# 4ButtonSwitch_Rev2_2.net
KiCad netlist of a schematic drawn in EAGLE
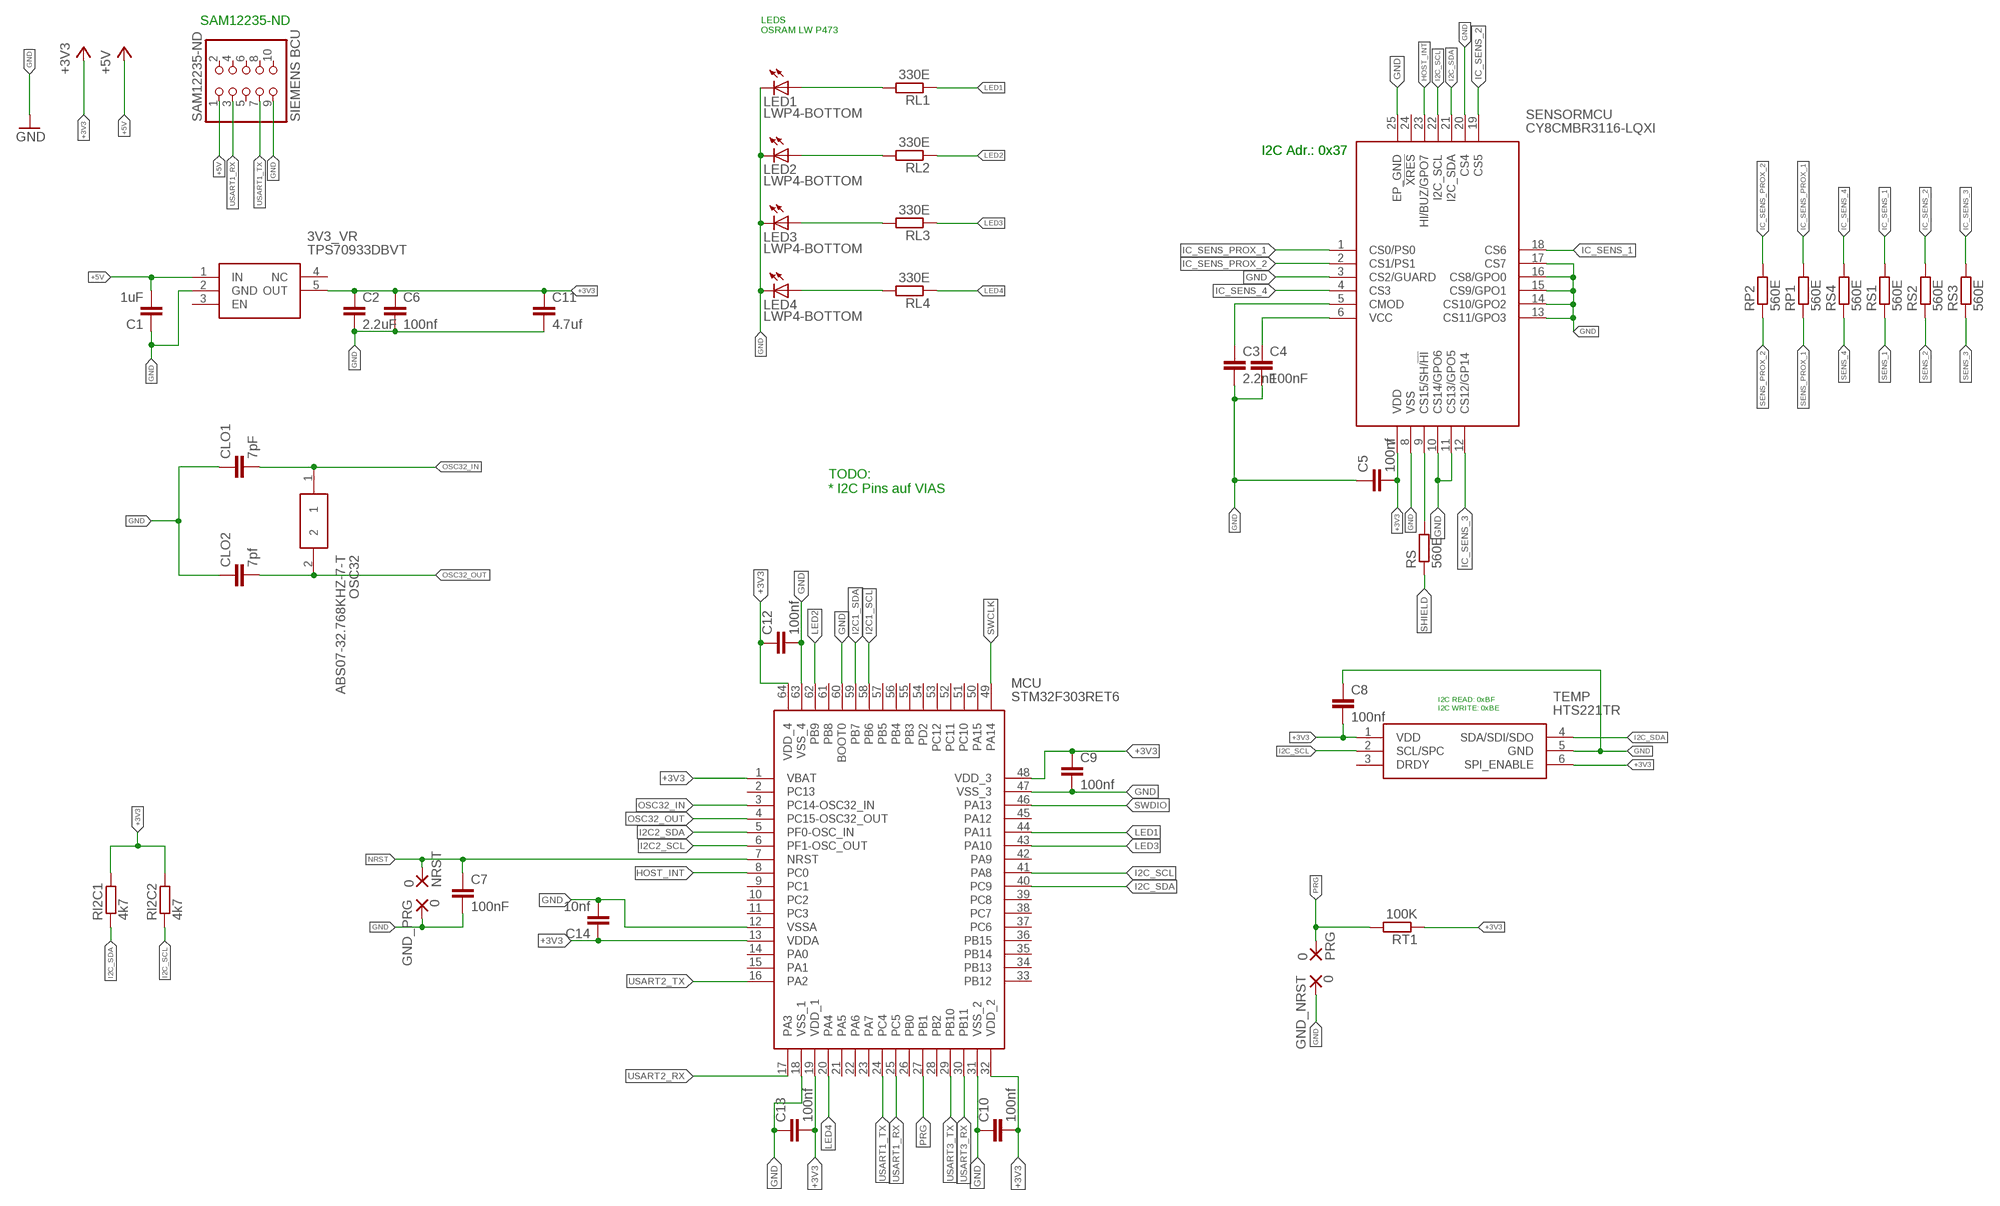
[diagram p0: schematic, sheet 1]

(export (version "E")
  (design (tool "Eeschema 10.0.6"))
  (components
    (comp (ref "3V3_VR")
      (value "TPS70933DBVT")
      (footprint "eagle-import:SOT95P280X145-5N")
      (fields (field (name "RS_PART_NUMBER") "8257033P"))
      (libsource (lib "eagle-import") (part "TPS70933DBVT"))
    )
    (comp (ref "C1")
      (value "1uF")
      (footprint "eagle-import:C0402")
      (libsource (lib "eagle-import") (part "C-EUC0402"))
    )
    (comp (ref "C2")
      (value "2.2uF")
      (footprint "eagle-import:C0402")
      (libsource (lib "eagle-import") (part "C-EUC0402"))
    )
    (comp (ref "C3")
      (value "2.2nF")
      (footprint "eagle-import:C0402")
      (libsource (lib "eagle-import") (part "C-EUC0402"))
    )
    (comp (ref "C4")
      (value "100nF")
      (footprint "eagle-import:C0402")
      (libsource (lib "eagle-import") (part "C-EUC0402"))
    )
    (comp (ref "C5")
      (value "100nf")
      (footprint "eagle-import:C0402")
      (libsource (lib "eagle-import") (part "C-EUC0402"))
    )
    (comp (ref "C6")
      (value "100nf")
      (footprint "eagle-import:C0402")
      (libsource (lib "eagle-import") (part "C-EUC0402"))
    )
    (comp (ref "C7")
      (value "100nF")
      (footprint "eagle-import:C0402")
      (libsource (lib "eagle-import") (part "C-EUC0402"))
    )
    (comp (ref "C8")
      (value "100nf")
      (footprint "eagle-import:C0402")
      (libsource (lib "eagle-import") (part "C-EUC0402"))
    )
    (comp (ref "C9")
      (value "100nf")
      (footprint "eagle-import:C0402")
      (libsource (lib "eagle-import") (part "C-EUC0402"))
    )
    (comp (ref "C10")
      (value "100nf")
      (footprint "eagle-import:C0402")
      (libsource (lib "eagle-import") (part "C-EUC0402"))
    )
    (comp (ref "C11")
      (value "4.7uf")
      (footprint "eagle-import:C0402")
      (libsource (lib "eagle-import") (part "C-EUC0402"))
    )
    (comp (ref "C12")
      (value "100nf")
      (footprint "eagle-import:C0402")
      (libsource (lib "eagle-import") (part "C-EUC0402"))
    )
    (comp (ref "C13")
      (value "100nf")
      (footprint "eagle-import:C0402")
      (libsource (lib "eagle-import") (part "C-EUC0402"))
    )
    (comp (ref "C14")
      (value "10nf")
      (footprint "eagle-import:C0402")
      (libsource (lib "eagle-import") (part "C-EUC0402"))
    )
    (comp (ref "CLO1")
      (value "7pF")
      (footprint "eagle-import:C0402")
      (libsource (lib "eagle-import") (part "C-EUC0402"))
    )
    (comp (ref "CLO2")
      (value "7pf")
      (footprint "eagle-import:C0402")
      (libsource (lib "eagle-import") (part "C-EUC0402"))
    )
    (comp (ref "GND_NRST")
      (value "0")
      (footprint "eagle-import:SMD2,54-5,08")
      (libsource (lib "eagle-import") (part "SMD5"))
    )
    (comp (ref "GND_PRG")
      (value "0")
      (footprint "eagle-import:SMD2,54-5,08")
      (libsource (lib "eagle-import") (part "SMD5"))
    )
    (comp (ref "LED1")
      (value "LWP4-BOTTOM")
      (footprint "eagle-import:P47F-BOTTOM")
      (libsource (lib "eagle-import") (part "P4-BOTTOMLW"))
    )
    (comp (ref "LED2")
      (value "LWP4-BOTTOM")
      (footprint "eagle-import:P47F-BOTTOM")
      (libsource (lib "eagle-import") (part "P4-BOTTOMLW"))
    )
    (comp (ref "LED3")
      (value "LWP4-BOTTOM")
      (footprint "eagle-import:P47F-BOTTOM")
      (libsource (lib "eagle-import") (part "P4-BOTTOMLW"))
    )
    (comp (ref "LED4")
      (value "LWP4-BOTTOM")
      (footprint "eagle-import:P47F-BOTTOM")
      (libsource (lib "eagle-import") (part "P4-BOTTOMLW"))
    )
    (comp (ref "MCU")
      (value "STM32F303RET6")
      (footprint "eagle-import:QFP50P1200X1200X160-64N")
      (fields (field (name "RS_PART_NUMBER") "1458887"))
      (libsource (lib "eagle-import") (part "STM32F303RET6"))
    )
    (comp (ref "NRST")
      (value "0")
      (footprint "eagle-import:SMD2,54-5,08")
      (libsource (lib "eagle-import") (part "SMD5"))
    )
    (comp (ref "OSC32")
      (value "ABS07-32.768KHZ-7-T")
      (footprint "eagle-import:ABS-07")
      (fields (field (name "RS_PART_NUMBER") "1712773P"))
      (libsource (lib "eagle-import") (part "ABS07-32.768KHZ-7-T"))
    )
    (comp (ref "PRG")
      (value "0")
      (footprint "eagle-import:SMD2,54-5,08")
      (libsource (lib "eagle-import") (part "SMD5"))
    )
    (comp (ref "RI2C1")
      (value "4k7")
      (footprint "eagle-import:R0402")
      (libsource (lib "eagle-import") (part "R-EU_R0402"))
    )
    (comp (ref "RI2C2")
      (value "4k7")
      (footprint "eagle-import:R0402")
      (libsource (lib "eagle-import") (part "R-EU_R0402"))
    )
    (comp (ref "RL1")
      (value "330E")
      (footprint "eagle-import:R0402")
      (libsource (lib "eagle-import") (part "R-EU_R0402"))
    )
    (comp (ref "RL2")
      (value "330E")
      (footprint "eagle-import:R0402")
      (libsource (lib "eagle-import") (part "R-EU_R0402"))
    )
    (comp (ref "RL3")
      (value "330E")
      (footprint "eagle-import:R0402")
      (libsource (lib "eagle-import") (part "R-EU_R0402"))
    )
    (comp (ref "RL4")
      (value "330E")
      (footprint "eagle-import:R0402")
      (libsource (lib "eagle-import") (part "R-EU_R0402"))
    )
    (comp (ref "RP1")
      (value "560E")
      (footprint "eagle-import:R0402")
      (libsource (lib "eagle-import") (part "R-EU_R0402"))
    )
    (comp (ref "RP2")
      (value "560E")
      (footprint "eagle-import:R0402")
      (libsource (lib "eagle-import") (part "R-EU_R0402"))
    )
    (comp (ref "RS")
      (value "560E")
      (footprint "eagle-import:R0402")
      (libsource (lib "eagle-import") (part "R-EU_R0402"))
    )
    (comp (ref "RS1")
      (value "560E")
      (footprint "eagle-import:R0402")
      (libsource (lib "eagle-import") (part "R-EU_R0402"))
    )
    (comp (ref "RS2")
      (value "560E")
      (footprint "eagle-import:R0402")
      (libsource (lib "eagle-import") (part "R-EU_R0402"))
    )
    (comp (ref "RS3")
      (value "560E")
      (footprint "eagle-import:R0402")
      (libsource (lib "eagle-import") (part "R-EU_R0402"))
    )
    (comp (ref "RS4")
      (value "560E")
      (footprint "eagle-import:R0402")
      (libsource (lib "eagle-import") (part "R-EU_R0402"))
    )
    (comp (ref "RT1")
      (value "100K")
      (footprint "eagle-import:R0402")
      (libsource (lib "eagle-import") (part "R-EU_R0402"))
    )
    (comp (ref "SAM12235-ND")
      (value "SIEMENS BCU")
      (footprint "eagle-import:2X05SMD")
      (libsource (lib "eagle-import") (part "PINHD-2X5_2.54-SMD"))
    )
    (comp (ref "SENSORMCU")
      (value "CY8CMBR3116-LQXI")
      (footprint "eagle-import:QFN50P400X400X60-25N")
      (fields (field (name "RS_PART_NUMBER") "1242976P"))
      (libsource (lib "eagle-import") (part "CY8CMBR3116-LQXI"))
    )
    (comp (ref "TEMP")
      (value "HTS221TR")
      (footprint "eagle-import:HLGA-6L")
      (fields (field (name "RS_PART_NUMBER") "1660935"))
      (libsource (lib "eagle-import") (part "HTS221TR"))
    )
  )
  (nets
    (net (code "1") (name "+3V3") (class "Default")
      (node (ref "3V3_VR") (pin "5") (pinfunction "OUT_5") (pintype "bidirectional"))
      (node (ref "C10") (pin "2") (pinfunction "2_2") (pintype "passive"))
      (node (ref "C11") (pin "1") (pinfunction "1_1") (pintype "passive"))
      (node (ref "C12") (pin "1") (pinfunction "1_1") (pintype "passive"))
      (node (ref "C13") (pin "2") (pinfunction "2_2") (pintype "passive"))
      (node (ref "C14") (pin "1") (pinfunction "1_1") (pintype "passive"))
      (node (ref "C2") (pin "1") (pinfunction "1_1") (pintype "passive"))
      (node (ref "C5") (pin "2") (pinfunction "2_2") (pintype "passive"))
      (node (ref "C6") (pin "1") (pinfunction "1_1") (pintype "passive"))
      (node (ref "C8") (pin "2") (pinfunction "2_2") (pintype "passive"))
      (node (ref "C9") (pin "1") (pinfunction "1_1") (pintype "passive"))
      (node (ref "MCU") (pin "1") (pinfunction "VBAT_1") (pintype "power_in"))
      (node (ref "MCU") (pin "13") (pinfunction "VDDA_13") (pintype "power_in"))
      (node (ref "MCU") (pin "19") (pinfunction "VDD_1_19") (pintype "power_in"))
      (node (ref "MCU") (pin "32") (pinfunction "VDD_2_32") (pintype "power_in"))
      (node (ref "MCU") (pin "48") (pinfunction "VDD_3_48") (pintype "power_in"))
      (node (ref "MCU") (pin "64") (pinfunction "VDD_4_64") (pintype "power_in"))
      (node (ref "RI2C1") (pin "2") (pinfunction "2_2") (pintype "passive"))
      (node (ref "RI2C2") (pin "2") (pinfunction "2_2") (pintype "passive"))
      (node (ref "RT1") (pin "1") (pinfunction "1_1") (pintype "passive"))
      (node (ref "SENSORMCU") (pin "7") (pinfunction "VDD_7") (pintype "power_in"))
      (node (ref "TEMP") (pin "1") (pinfunction "VDD_1") (pintype "bidirectional"))
      (node (ref "TEMP") (pin "6") (pinfunction "SPI_ENABLE_6") (pintype "bidirectional"))
    )
    (net (code "2") (name "+5V") (class "Default")
      (node (ref "3V3_VR") (pin "1") (pinfunction "IN_1") (pintype "bidirectional"))
      (node (ref "C1") (pin "2") (pinfunction "2_2") (pintype "passive"))
      (node (ref "SAM12235-ND") (pin "1") (pinfunction "1_1") (pintype "passive"))
    )
    (net (code "3") (name "GND") (class "Default")
      (node (ref "3V3_VR") (pin "2") (pinfunction "GND_2") (pintype "bidirectional"))
      (node (ref "C1") (pin "1") (pinfunction "1_1") (pintype "passive"))
      (node (ref "C10") (pin "1") (pinfunction "1_1") (pintype "passive"))
      (node (ref "C11") (pin "2") (pinfunction "2_2") (pintype "passive"))
      (node (ref "C12") (pin "2") (pinfunction "2_2") (pintype "passive"))
      (node (ref "C13") (pin "1") (pinfunction "1_1") (pintype "passive"))
      (node (ref "C14") (pin "2") (pinfunction "2_2") (pintype "passive"))
      (node (ref "C2") (pin "2") (pinfunction "2_2") (pintype "passive"))
      (node (ref "C3") (pin "2") (pinfunction "2_2") (pintype "passive"))
      (node (ref "C4") (pin "2") (pinfunction "2_2") (pintype "passive"))
      (node (ref "C5") (pin "1") (pinfunction "1_1") (pintype "passive"))
      (node (ref "C6") (pin "2") (pinfunction "2_2") (pintype "passive"))
      (node (ref "C7") (pin "2") (pinfunction "2_2") (pintype "passive"))
      (node (ref "C8") (pin "1") (pinfunction "1_1") (pintype "passive"))
      (node (ref "C9") (pin "2") (pinfunction "2_2") (pintype "passive"))
      (node (ref "CLO1") (pin "1") (pinfunction "1_1") (pintype "passive"))
      (node (ref "CLO2") (pin "1") (pinfunction "1_1") (pintype "passive"))
      (node (ref "GND_NRST") (pin "1") (pinfunction "P_1") (pintype "passive"))
      (node (ref "GND_PRG") (pin "1") (pinfunction "P_1") (pintype "passive"))
      (node (ref "LED1") (pin "C") (pinfunction "C_C") (pintype "passive"))
      (node (ref "LED2") (pin "C") (pinfunction "C_C") (pintype "passive"))
      (node (ref "LED3") (pin "C") (pinfunction "C_C") (pintype "passive"))
      (node (ref "LED4") (pin "C") (pinfunction "C_C") (pintype "passive"))
      (node (ref "MCU") (pin "12") (pinfunction "VSSA_12") (pintype "power_in"))
      (node (ref "MCU") (pin "18") (pinfunction "VSS_1_18") (pintype "power_in"))
      (node (ref "MCU") (pin "31") (pinfunction "VSS_2_31") (pintype "power_in"))
      (node (ref "MCU") (pin "47") (pinfunction "VSS_3_47") (pintype "power_in"))
      (node (ref "MCU") (pin "60") (pinfunction "BOOT0_60") (pintype "bidirectional"))
      (node (ref "MCU") (pin "63") (pinfunction "VSS_4_63") (pintype "power_in"))
      (node (ref "SAM12235-ND") (pin "9") (pinfunction "9_9") (pintype "passive"))
      (node (ref "SENSORMCU") (pin "10") (pinfunction "CS14/GPO6_10") (pintype "input"))
      (node (ref "SENSORMCU") (pin "11") (pinfunction "CS13/GPO5_11") (pintype "input"))
      (node (ref "SENSORMCU") (pin "13") (pinfunction "CS11/GPO3_13") (pintype "input"))
      (node (ref "SENSORMCU") (pin "14") (pinfunction "CS10/GPO2_14") (pintype "input"))
      (node (ref "SENSORMCU") (pin "15") (pinfunction "CS9/GPO1_15") (pintype "input"))
      (node (ref "SENSORMCU") (pin "16") (pinfunction "CS8/GPO0_16") (pintype "input"))
      (node (ref "SENSORMCU") (pin "17") (pinfunction "CS7_17") (pintype "input"))
      (node (ref "SENSORMCU") (pin "20") (pinfunction "CS4_20") (pintype "input"))
      (node (ref "SENSORMCU") (pin "25") (pinfunction "EP_GND_25") (pintype "power_in"))
      (node (ref "SENSORMCU") (pin "3") (pinfunction "CS2/GUARD_3") (pintype "input"))
      (node (ref "SENSORMCU") (pin "8") (pinfunction "VSS_8") (pintype "power_in"))
      (node (ref "TEMP") (pin "5") (pinfunction "GND_5") (pintype "bidirectional"))
    )
    (net (code "4") (name "HOST_INT") (class "Default")
      (node (ref "MCU") (pin "8") (pinfunction "PC0_8") (pintype "bidirectional"))
      (node (ref "SENSORMCU") (pin "23") (pinfunction "HI/BUZ/GPO7_23") (pintype "bidirectional"))
    )
    (net (code "5") (name "I2C1_SCL") (class "Default")
      (node (ref "MCU") (pin "58") (pinfunction "PB6_58") (pintype "bidirectional"))
    )
    (net (code "6") (name "I2C1_SDA") (class "Default")
      (node (ref "MCU") (pin "59") (pinfunction "PB7_59") (pintype "bidirectional"))
    )
    (net (code "7") (name "I2C2_SCL") (class "Default")
      (node (ref "MCU") (pin "6") (pinfunction "PF1-OSC_OUT_6") (pintype "bidirectional"))
    )
    (net (code "8") (name "I2C2_SDA") (class "Default")
      (node (ref "MCU") (pin "5") (pinfunction "PF0-OSC_IN_5") (pintype "bidirectional"))
    )
    (net (code "9") (name "I2C_SCL") (class "Default")
      (node (ref "MCU") (pin "41") (pinfunction "PA8_41") (pintype "bidirectional"))
      (node (ref "RI2C2") (pin "1") (pinfunction "1_1") (pintype "passive"))
      (node (ref "SENSORMCU") (pin "22") (pinfunction "I2C_SCL_22") (pintype "bidirectional"))
      (node (ref "TEMP") (pin "2") (pinfunction "SCL/SPC_2") (pintype "bidirectional"))
    )
    (net (code "10") (name "I2C_SDA") (class "Default")
      (node (ref "MCU") (pin "40") (pinfunction "PC9_40") (pintype "bidirectional"))
      (node (ref "RI2C1") (pin "1") (pinfunction "1_1") (pintype "passive"))
      (node (ref "SENSORMCU") (pin "21") (pinfunction "I2C_SDA_21") (pintype "bidirectional"))
      (node (ref "TEMP") (pin "4") (pinfunction "SDA/SDI/SDO_4") (pintype "bidirectional"))
    )
    (net (code "11") (name "IC_SENS_1") (class "Default")
      (node (ref "RS1") (pin "2") (pinfunction "2_2") (pintype "passive"))
      (node (ref "SENSORMCU") (pin "18") (pinfunction "CS6_18") (pintype "input"))
    )
    (net (code "12") (name "IC_SENS_2") (class "Default")
      (node (ref "RS2") (pin "2") (pinfunction "2_2") (pintype "passive"))
      (node (ref "SENSORMCU") (pin "19") (pinfunction "CS5_19") (pintype "input"))
    )
    (net (code "13") (name "IC_SENS_3") (class "Default")
      (node (ref "RS3") (pin "2") (pinfunction "2_2") (pintype "passive"))
      (node (ref "SENSORMCU") (pin "12") (pinfunction "CS12/GP14_12") (pintype "input"))
    )
    (net (code "14") (name "IC_SENS_4") (class "Default")
      (node (ref "RS4") (pin "2") (pinfunction "2_2") (pintype "passive"))
      (node (ref "SENSORMCU") (pin "4") (pinfunction "CS3_4") (pintype "input"))
    )
    (net (code "15") (name "IC_SENS_PROX_1") (class "Default")
      (node (ref "RP1") (pin "2") (pinfunction "2_2") (pintype "passive"))
      (node (ref "SENSORMCU") (pin "1") (pinfunction "CS0/PS0_1") (pintype "input"))
    )
    (net (code "16") (name "IC_SENS_PROX_2") (class "Default")
      (node (ref "RP2") (pin "2") (pinfunction "2_2") (pintype "passive"))
      (node (ref "SENSORMCU") (pin "2") (pinfunction "CS1/PS1_2") (pintype "input"))
    )
    (net (code "17") (name "LED1") (class "Default")
      (node (ref "MCU") (pin "44") (pinfunction "PA11_44") (pintype "bidirectional"))
      (node (ref "RL1") (pin "1") (pinfunction "1_1") (pintype "passive"))
    )
    (net (code "18") (name "LED2") (class "Default")
      (node (ref "MCU") (pin "62") (pinfunction "PB9_62") (pintype "bidirectional"))
      (node (ref "RL2") (pin "1") (pinfunction "1_1") (pintype "passive"))
    )
    (net (code "19") (name "LED3") (class "Default")
      (node (ref "MCU") (pin "43") (pinfunction "PA10_43") (pintype "bidirectional"))
      (node (ref "RL3") (pin "1") (pinfunction "1_1") (pintype "passive"))
    )
    (net (code "20") (name "LED4") (class "Default")
      (node (ref "MCU") (pin "20") (pinfunction "PA4_20") (pintype "bidirectional"))
      (node (ref "RL4") (pin "1") (pinfunction "1_1") (pintype "passive"))
    )
    (net (code "21") (name "NRST") (class "Default")
      (node (ref "C7") (pin "1") (pinfunction "1_1") (pintype "passive"))
      (node (ref "MCU") (pin "7") (pinfunction "NRST_7") (pintype "bidirectional"))
      (node (ref "NRST") (pin "1") (pinfunction "P_1") (pintype "passive"))
    )
    (net (code "22") (name "Net-(LED1-PadA)") (class "Default")
      (node (ref "LED1") (pin "A") (pinfunction "A_A") (pintype "passive"))
      (node (ref "RL1") (pin "2") (pinfunction "2_2") (pintype "passive"))
    )
    (net (code "23") (name "Net-(LED2-PadA)") (class "Default")
      (node (ref "LED2") (pin "A") (pinfunction "A_A") (pintype "passive"))
      (node (ref "RL2") (pin "2") (pinfunction "2_2") (pintype "passive"))
    )
    (net (code "24") (name "Net-(LED3-PadA)") (class "Default")
      (node (ref "LED3") (pin "A") (pinfunction "A_A") (pintype "passive"))
      (node (ref "RL3") (pin "2") (pinfunction "2_2") (pintype "passive"))
    )
    (net (code "25") (name "Net-(LED4-PadA)") (class "Default")
      (node (ref "LED4") (pin "A") (pinfunction "A_A") (pintype "passive"))
      (node (ref "RL4") (pin "2") (pinfunction "2_2") (pintype "passive"))
    )
    (net (code "26") (name "Net-(SENSORMCU-CMOD)") (class "Default")
      (node (ref "C3") (pin "1") (pinfunction "1_1") (pintype "passive"))
      (node (ref "SENSORMCU") (pin "5") (pinfunction "CMOD_5") (pintype "bidirectional"))
    )
    (net (code "27") (name "Net-(SENSORMCU-CS15{slash}SH{slash}~{HI})") (class "Default")
      (node (ref "RS") (pin "2") (pinfunction "2_2") (pintype "passive"))
      (node (ref "SENSORMCU") (pin "9") (pinfunction "CS15/SH/~{HI}_9") (pintype "input"))
    )
    (net (code "28") (name "Net-(SENSORMCU-VCC)") (class "Default")
      (node (ref "C4") (pin "1") (pinfunction "1_1") (pintype "passive"))
      (node (ref "SENSORMCU") (pin "6") (pinfunction "VCC_6") (pintype "power_in"))
    )
    (net (code "29") (name "OSC32_IN") (class "Default")
      (node (ref "CLO1") (pin "2") (pinfunction "2_2") (pintype "passive"))
      (node (ref "MCU") (pin "3") (pinfunction "PC14-OSC32_IN_3") (pintype "bidirectional"))
      (node (ref "OSC32") (pin "1") (pinfunction "1_1") (pintype "bidirectional"))
    )
    (net (code "30") (name "OSC32_OUT") (class "Default")
      (node (ref "CLO2") (pin "2") (pinfunction "2_2") (pintype "passive"))
      (node (ref "MCU") (pin "4") (pinfunction "PC15-OSC32_OUT_4") (pintype "bidirectional"))
      (node (ref "OSC32") (pin "2") (pinfunction "2_2") (pintype "bidirectional"))
    )
    (net (code "31") (name "PRG") (class "Default")
      (node (ref "MCU") (pin "27") (pinfunction "PB1_27") (pintype "bidirectional"))
      (node (ref "PRG") (pin "1") (pinfunction "P_1") (pintype "passive"))
      (node (ref "RT1") (pin "2") (pinfunction "2_2") (pintype "passive"))
    )
    (net (code "32") (name "SENS_1") (class "Default")
      (node (ref "RS1") (pin "1") (pinfunction "1_1") (pintype "passive"))
    )
    (net (code "33") (name "SENS_2") (class "Default")
      (node (ref "RS2") (pin "1") (pinfunction "1_1") (pintype "passive"))
    )
    (net (code "34") (name "SENS_3") (class "Default")
      (node (ref "RS3") (pin "1") (pinfunction "1_1") (pintype "passive"))
    )
    (net (code "35") (name "SENS_4") (class "Default")
      (node (ref "RS4") (pin "1") (pinfunction "1_1") (pintype "passive"))
    )
    (net (code "36") (name "SENS_PROX_1") (class "Default")
      (node (ref "RP1") (pin "1") (pinfunction "1_1") (pintype "passive"))
    )
    (net (code "37") (name "SENS_PROX_2") (class "Default")
      (node (ref "RP2") (pin "1") (pinfunction "1_1") (pintype "passive"))
    )
    (net (code "38") (name "SHIELD") (class "Default")
      (node (ref "RS") (pin "1") (pinfunction "1_1") (pintype "passive"))
    )
    (net (code "39") (name "SWCLK") (class "Default")
      (node (ref "MCU") (pin "49") (pinfunction "PA14_49") (pintype "bidirectional"))
    )
    (net (code "40") (name "SWDIO") (class "Default")
      (node (ref "MCU") (pin "46") (pinfunction "PA13_46") (pintype "bidirectional"))
    )
    (net (code "41") (name "USART1_RX") (class "Default")
      (node (ref "MCU") (pin "25") (pinfunction "PC5_25") (pintype "bidirectional"))
      (node (ref "SAM12235-ND") (pin "3") (pinfunction "3_3") (pintype "passive"))
    )
    (net (code "42") (name "USART1_TX") (class "Default")
      (node (ref "MCU") (pin "24") (pinfunction "PC4_24") (pintype "bidirectional"))
      (node (ref "SAM12235-ND") (pin "7") (pinfunction "7_7") (pintype "passive"))
    )
    (net (code "43") (name "USART2_RX") (class "Default")
      (node (ref "MCU") (pin "17") (pinfunction "PA3_17") (pintype "bidirectional"))
    )
    (net (code "44") (name "USART2_TX") (class "Default")
      (node (ref "MCU") (pin "16") (pinfunction "PA2_16") (pintype "bidirectional"))
    )
    (net (code "45") (name "USART3_RX") (class "Default")
      (node (ref "MCU") (pin "30") (pinfunction "PB11_30") (pintype "bidirectional"))
    )
    (net (code "46") (name "USART3_TX") (class "Default")
      (node (ref "MCU") (pin "29") (pinfunction "PB10_29") (pintype "bidirectional"))
    )
    (net (code "47") (name "unconnected-(3V3_VR-EN-Pad3)") (class "Default")
      (node (ref "3V3_VR") (pin "3") (pinfunction "EN_3") (pintype "bidirectional"))
    )
    (net (code "48") (name "unconnected-(3V3_VR-NC-Pad4)") (class "Default")
      (node (ref "3V3_VR") (pin "4") (pinfunction "NC_4") (pintype "no_connect"))
    )
    (net (code "49") (name "unconnected-(MCU-PA0-Pad14)") (class "Default")
      (node (ref "MCU") (pin "14") (pinfunction "PA0_14") (pintype "bidirectional"))
    )
    (net (code "50") (name "unconnected-(MCU-PA1-Pad15)") (class "Default")
      (node (ref "MCU") (pin "15") (pinfunction "PA1_15") (pintype "bidirectional"))
    )
    (net (code "51") (name "unconnected-(MCU-PA5-Pad21)") (class "Default")
      (node (ref "MCU") (pin "21") (pinfunction "PA5_21") (pintype "bidirectional"))
    )
    (net (code "52") (name "unconnected-(MCU-PA6-Pad22)") (class "Default")
      (node (ref "MCU") (pin "22") (pinfunction "PA6_22") (pintype "bidirectional"))
    )
    (net (code "53") (name "unconnected-(MCU-PA7-Pad23)") (class "Default")
      (node (ref "MCU") (pin "23") (pinfunction "PA7_23") (pintype "bidirectional"))
    )
    (net (code "54") (name "unconnected-(MCU-PA9-Pad42)") (class "Default")
      (node (ref "MCU") (pin "42") (pinfunction "PA9_42") (pintype "bidirectional"))
    )
    (net (code "55") (name "unconnected-(MCU-PA12-Pad45)") (class "Default")
      (node (ref "MCU") (pin "45") (pinfunction "PA12_45") (pintype "bidirectional"))
    )
    (net (code "56") (name "unconnected-(MCU-PA15-Pad50)") (class "Default")
      (node (ref "MCU") (pin "50") (pinfunction "PA15_50") (pintype "bidirectional"))
    )
    (net (code "57") (name "unconnected-(MCU-PB0-Pad26)") (class "Default")
      (node (ref "MCU") (pin "26") (pinfunction "PB0_26") (pintype "bidirectional"))
    )
    (net (code "58") (name "unconnected-(MCU-PB2-Pad28)") (class "Default")
      (node (ref "MCU") (pin "28") (pinfunction "PB2_28") (pintype "bidirectional"))
    )
    (net (code "59") (name "unconnected-(MCU-PB3-Pad55)") (class "Default")
      (node (ref "MCU") (pin "55") (pinfunction "PB3_55") (pintype "bidirectional"))
    )
    (net (code "60") (name "unconnected-(MCU-PB4-Pad56)") (class "Default")
      (node (ref "MCU") (pin "56") (pinfunction "PB4_56") (pintype "bidirectional"))
    )
    (net (code "61") (name "unconnected-(MCU-PB5-Pad57)") (class "Default")
      (node (ref "MCU") (pin "57") (pinfunction "PB5_57") (pintype "bidirectional"))
    )
    (net (code "62") (name "unconnected-(MCU-PB8-Pad61)") (class "Default")
      (node (ref "MCU") (pin "61") (pinfunction "PB8_61") (pintype "bidirectional"))
    )
    (net (code "63") (name "unconnected-(MCU-PB12-Pad33)") (class "Default")
      (node (ref "MCU") (pin "33") (pinfunction "PB12_33") (pintype "bidirectional"))
    )
    (net (code "64") (name "unconnected-(MCU-PB13-Pad34)") (class "Default")
      (node (ref "MCU") (pin "34") (pinfunction "PB13_34") (pintype "bidirectional"))
    )
    (net (code "65") (name "unconnected-(MCU-PB14-Pad35)") (class "Default")
      (node (ref "MCU") (pin "35") (pinfunction "PB14_35") (pintype "bidirectional"))
    )
    (net (code "66") (name "unconnected-(MCU-PB15-Pad36)") (class "Default")
      (node (ref "MCU") (pin "36") (pinfunction "PB15_36") (pintype "bidirectional"))
    )
    (net (code "67") (name "unconnected-(MCU-PC1-Pad9)") (class "Default")
      (node (ref "MCU") (pin "9") (pinfunction "PC1_9") (pintype "bidirectional"))
    )
    (net (code "68") (name "unconnected-(MCU-PC2-Pad10)") (class "Default")
      (node (ref "MCU") (pin "10") (pinfunction "PC2_10") (pintype "bidirectional"))
    )
    (net (code "69") (name "unconnected-(MCU-PC3-Pad11)") (class "Default")
      (node (ref "MCU") (pin "11") (pinfunction "PC3_11") (pintype "bidirectional"))
    )
    (net (code "70") (name "unconnected-(MCU-PC6-Pad37)") (class "Default")
      (node (ref "MCU") (pin "37") (pinfunction "PC6_37") (pintype "bidirectional"))
    )
    (net (code "71") (name "unconnected-(MCU-PC7-Pad38)") (class "Default")
      (node (ref "MCU") (pin "38") (pinfunction "PC7_38") (pintype "bidirectional"))
    )
    (net (code "72") (name "unconnected-(MCU-PC8-Pad39)") (class "Default")
      (node (ref "MCU") (pin "39") (pinfunction "PC8_39") (pintype "bidirectional"))
    )
    (net (code "73") (name "unconnected-(MCU-PC10-Pad51)") (class "Default")
      (node (ref "MCU") (pin "51") (pinfunction "PC10_51") (pintype "bidirectional"))
    )
    (net (code "74") (name "unconnected-(MCU-PC11-Pad52)") (class "Default")
      (node (ref "MCU") (pin "52") (pinfunction "PC11_52") (pintype "bidirectional"))
    )
    (net (code "75") (name "unconnected-(MCU-PC12-Pad53)") (class "Default")
      (node (ref "MCU") (pin "53") (pinfunction "PC12_53") (pintype "bidirectional"))
    )
    (net (code "76") (name "unconnected-(MCU-PC13-Pad2)") (class "Default")
      (node (ref "MCU") (pin "2") (pinfunction "PC13_2") (pintype "bidirectional"))
    )
    (net (code "77") (name "unconnected-(MCU-PD2-Pad54)") (class "Default")
      (node (ref "MCU") (pin "54") (pinfunction "PD2_54") (pintype "bidirectional"))
    )
    (net (code "78") (name "unconnected-(SAM12235-ND-Pad2)") (class "Default")
      (node (ref "SAM12235-ND") (pin "2") (pinfunction "2_2") (pintype "passive"))
    )
    (net (code "79") (name "unconnected-(SAM12235-ND-Pad4)") (class "Default")
      (node (ref "SAM12235-ND") (pin "4") (pinfunction "4_4") (pintype "passive"))
    )
    (net (code "80") (name "unconnected-(SAM12235-ND-Pad5)") (class "Default")
      (node (ref "SAM12235-ND") (pin "5") (pinfunction "5_5") (pintype "passive"))
    )
    (net (code "81") (name "unconnected-(SAM12235-ND-Pad6)") (class "Default")
      (node (ref "SAM12235-ND") (pin "6") (pinfunction "6_6") (pintype "passive"))
    )
    (net (code "82") (name "unconnected-(SAM12235-ND-Pad8)") (class "Default")
      (node (ref "SAM12235-ND") (pin "8") (pinfunction "8_8") (pintype "passive"))
    )
    (net (code "83") (name "unconnected-(SAM12235-ND-Pad10)") (class "Default")
      (node (ref "SAM12235-ND") (pin "10") (pinfunction "10_10") (pintype "passive"))
    )
    (net (code "84") (name "unconnected-(SENSORMCU-~{XRES}-Pad24)") (class "Default")
      (node (ref "SENSORMCU") (pin "24") (pinfunction "~{XRES}_24") (pintype "bidirectional"))
    )
    (net (code "85") (name "unconnected-(TEMP-DRDY-Pad3)") (class "Default")
      (node (ref "TEMP") (pin "3") (pinfunction "DRDY_3") (pintype "bidirectional"))
    )
  )
)
